# ne555_timer.net
KiCad netlist of a schematic drawn in Altium Designer
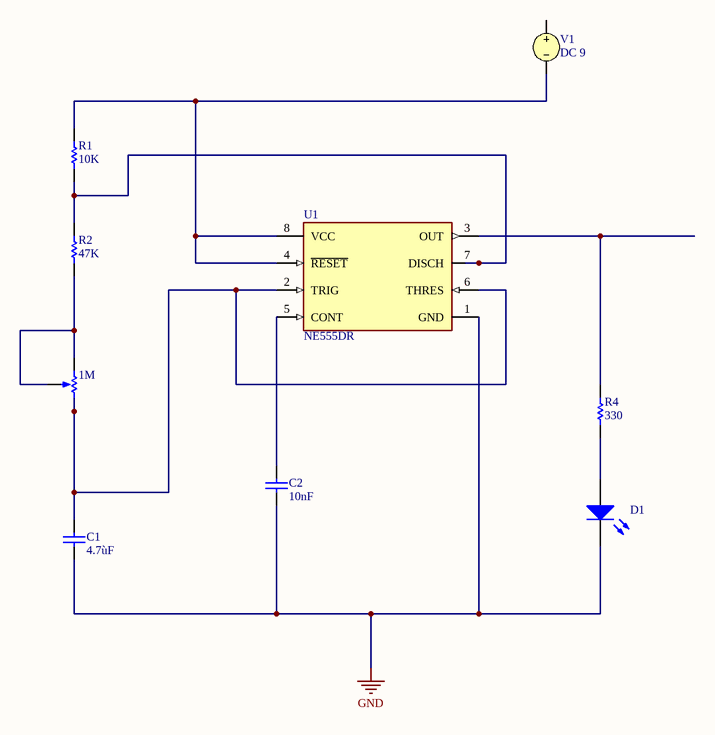
[diagram p0: ne555 timer.SchDoc]

(export (version "E")
  (design (tool "Eeschema 10.0.6"))
  (components
    (comp (ref "1M")
      (value "Potentiometer")
      (libsource (lib "Simulation Generic Components") (part "Potentiometer"))
    )
    (comp (ref "C1")
      (value "4.7ùF")
      (description "Capacitor")
      (libsource (lib "Simulation Generic Components") (part "Capacitor"))
    )
    (comp (ref "C2")
      (value "10nF")
      (description "Capacitor")
      (libsource (lib "Simulation Generic Components") (part "Capacitor"))
    )
    (comp (ref "D1")
      (value "Light-Emitting Diode")
      (libsource (lib "Simulation Generic Components") (part "LED"))
    )
    (comp (ref "R1")
      (value "10K")
      (description "Resistor")
      (libsource (lib "Simulation Generic Components") (part "Resistor"))
    )
    (comp (ref "R2")
      (value "47K")
      (description "Resistor")
      (libsource (lib "Simulation Generic Components") (part "Resistor"))
    )
    (comp (ref "R4")
      (value "330")
      (description "Resistor")
      (libsource (lib "Simulation Generic Components") (part "Resistor"))
    )
    (comp (ref "U1")
      (value "NE555DR")
      (footprint "FP-D0008A-IPC_A")
      (description "IC OSC SGL TIMER 100KHZ 8-SOIC")
      (libsource (lib "Altium Content Vault") (part "a29bba90211dec1890110b94dad7d53"))
    )
    (comp (ref "V1")
      (value "DC 9")
      (description "Voltage Source")
      (fields (field (name "PUBLISHER") "Altium Limited"))
      (libsource (lib "Simulation Generic Components") (part "VSRC"))
    )
  )
  (nets
    (net (code "1") (name "GND") (class "Default")
      (node (ref "C1") (pin "1") (pinfunction "1_1") (pintype "passive"))
      (node (ref "C2") (pin "1") (pinfunction "1_1") (pintype "passive"))
      (node (ref "D1") (pin "2") (pinfunction "K_2") (pintype "passive"))
      (node (ref "U1") (pin "1") (pinfunction "GND_1") (pintype "power_in"))
    )
    (net (code "2") (name "Net-(1M-BOT)") (class "Default")
      (node (ref "1M") (pin "2") (pinfunction "BOT_2") (pintype "passive"))
      (node (ref "C1") (pin "2") (pinfunction "2_2") (pintype "passive"))
      (node (ref "U1") (pin "2") (pinfunction "TRIG_2") (pintype "input"))
      (node (ref "U1") (pin "6") (pinfunction "THRES_6") (pintype "input"))
    )
    (net (code "3") (name "Net-(1M-TAP)") (class "Default")
      (node (ref "1M") (pin "1") (pinfunction "TOP_1") (pintype "passive"))
      (node (ref "1M") (pin "3") (pinfunction "TAP_3") (pintype "passive"))
      (node (ref "R2") (pin "1") (pinfunction "1_1") (pintype "passive"))
    )
    (net (code "4") (name "Net-(D1-A)") (class "Default")
      (node (ref "D1") (pin "1") (pinfunction "A_1") (pintype "passive"))
      (node (ref "R4") (pin "1") (pinfunction "1_1") (pintype "passive"))
    )
    (net (code "5") (name "Net-(U1-CONT)") (class "Default")
      (node (ref "C2") (pin "2") (pinfunction "2_2") (pintype "passive"))
      (node (ref "U1") (pin "5") (pinfunction "CONT_5") (pintype "input"))
    )
    (net (code "6") (name "Net-(U1-DISCH)") (class "Default")
      (node (ref "R1") (pin "1") (pinfunction "1_1") (pintype "passive"))
      (node (ref "R2") (pin "2") (pinfunction "2_2") (pintype "passive"))
      (node (ref "U1") (pin "7") (pinfunction "DISCH_7") (pintype "open_collector"))
    )
    (net (code "7") (name "Net-(U1-OUT)") (class "Default")
      (node (ref "R4") (pin "2") (pinfunction "2_2") (pintype "passive"))
      (node (ref "U1") (pin "3") (pinfunction "OUT_3") (pintype "output"))
    )
    (net (code "8") (name "Net-(U1-VCC)") (class "Default")
      (node (ref "R1") (pin "2") (pinfunction "2_2") (pintype "passive"))
      (node (ref "U1") (pin "4") (pinfunction "~{RESET}_4") (pintype "input"))
      (node (ref "U1") (pin "8") (pinfunction "VCC_8") (pintype "power_in"))
      (node (ref "V1") (pin "2") (pinfunction "2_2") (pintype "passive"))
    )
    (net (code "9") (name "unconnected-(V1-Pad1)") (class "Default")
      (node (ref "V1") (pin "1") (pinfunction "1_1") (pintype "passive"))
    )
  )
)
